# MotorSliderNoPower.net
KiCad netlist of a schematic drawn in EAGLE
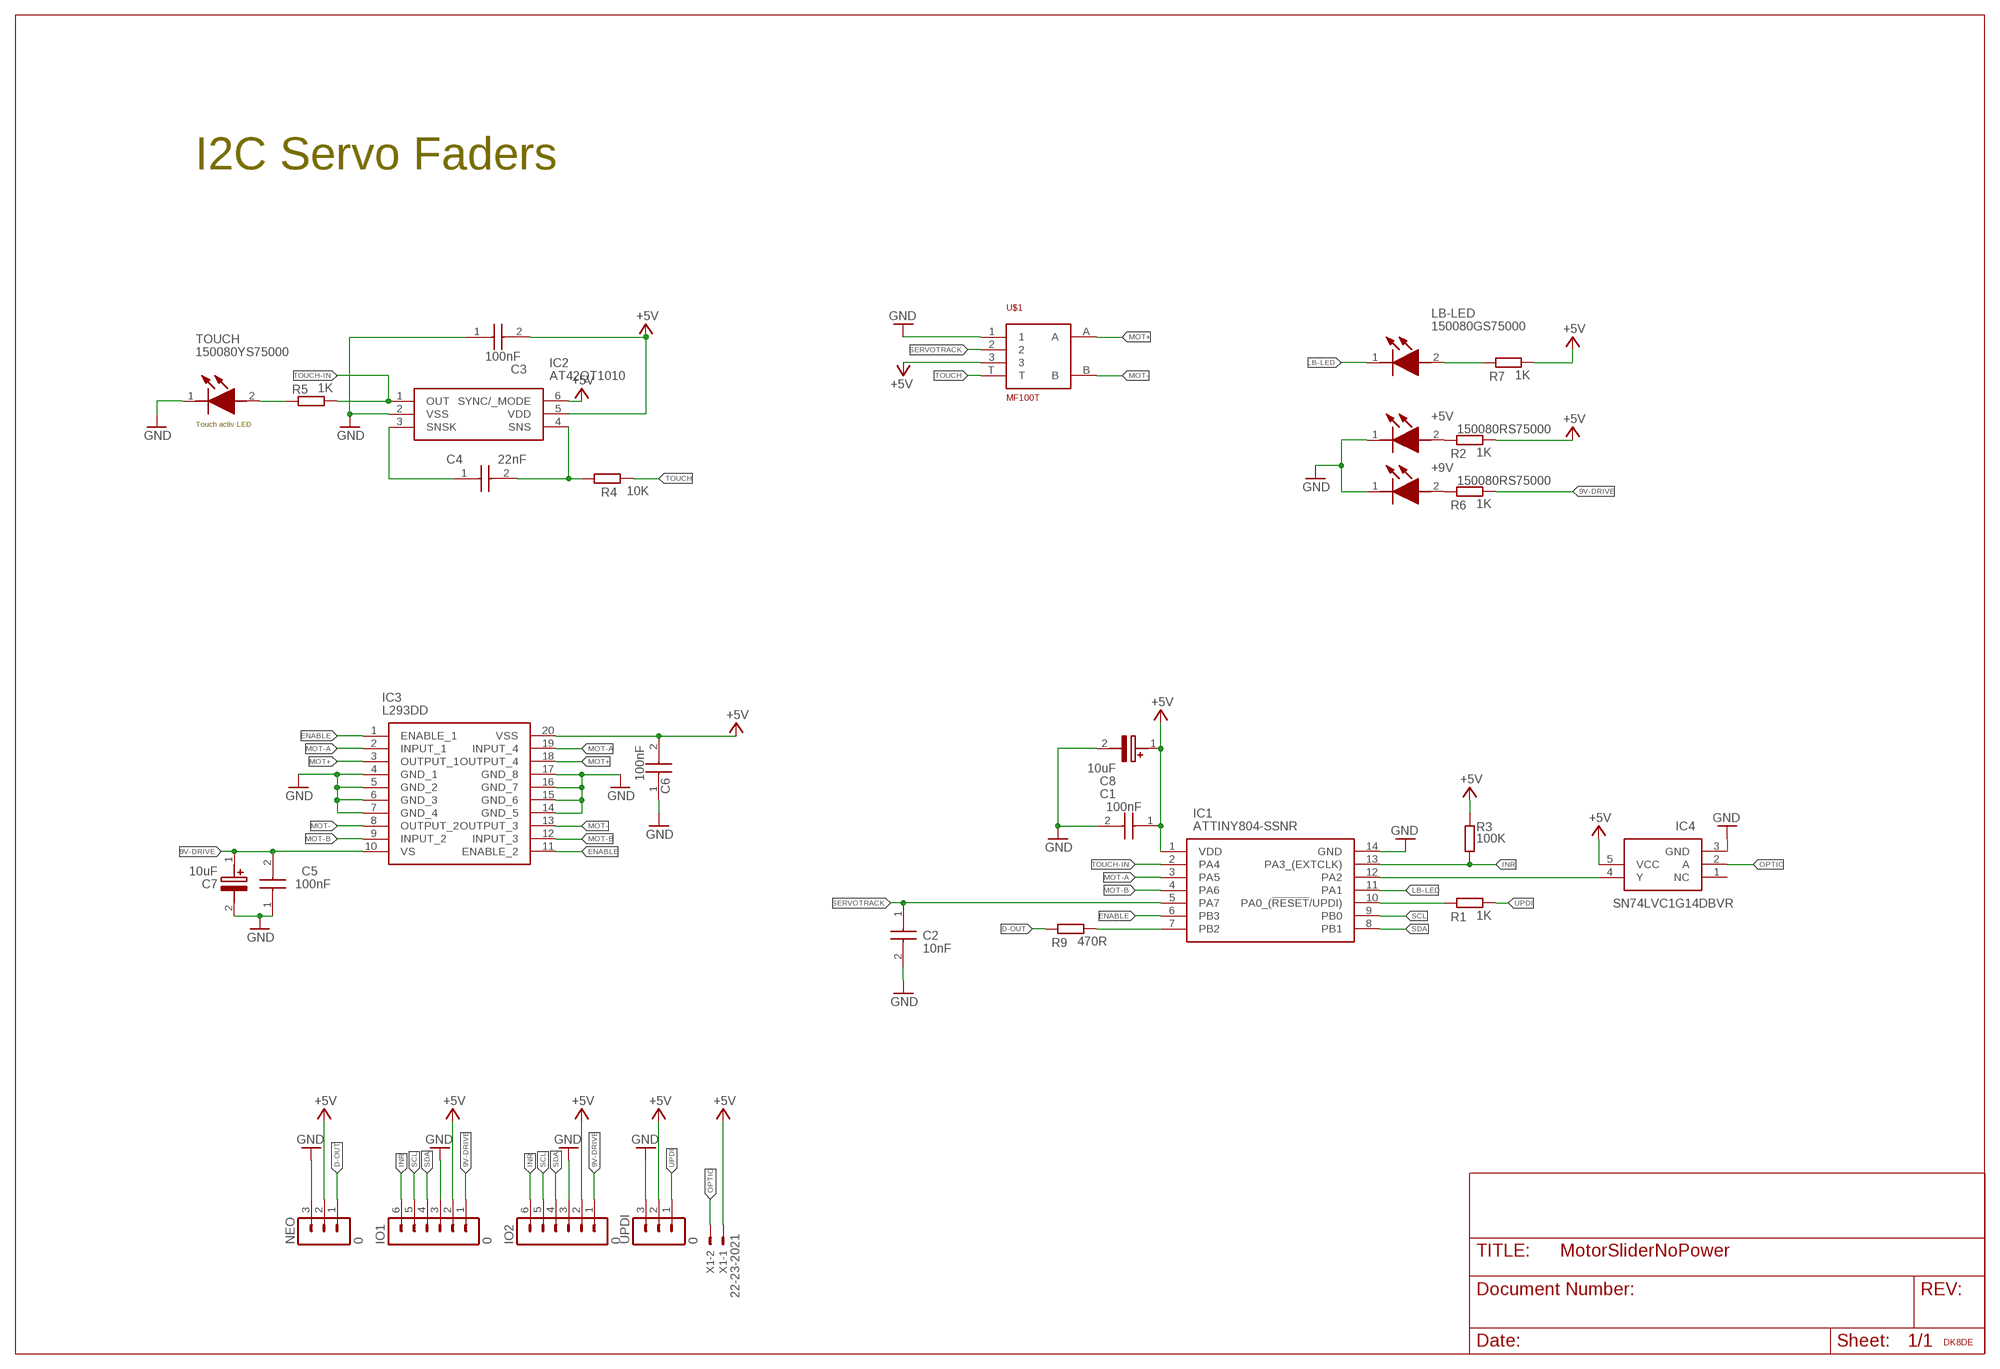
[diagram p0: schematic, sheet 1]

(export (version "E")
  (design (tool "Eeschema 10.0.6"))
  (components
    (comp (ref "+5V")
      (value "150080RS75000")
      (footprint "eagle-import:LEDC2012X80N")
      (fields (field (name "MOUSER_PART_NUMBER") "710-150080RS75000"))
      (libsource (lib "eagle-import") (part "150080RS75000"))
    )
    (comp (ref "+9V")
      (value "150080RS75000")
      (footprint "eagle-import:LEDC2012X80N")
      (fields (field (name "MOUSER_PART_NUMBER") "710-150080RS75000"))
      (libsource (lib "eagle-import") (part "150080RS75000"))
    )
    (comp (ref "C1")
      (value "100nF")
      (footprint "eagle-import:C0805")
      (fields
        (field (name "MANUFACTURER_PART_NUMBER") "C0805C104K1RACTU")
        (field (name "MOUSER_PART_NUMBER") "80-C0805C104K1R")
      )
      (libsource (lib "eagle-import") (part "C0805C104K1RACTU"))
    )
    (comp (ref "C2")
      (value "10nF")
      (footprint "eagle-import:C0805")
      (fields
        (field (name "MANUFACTURER_PART_NUMBER") "C0805Y103K4RACTU")
        (field (name "MOUSER_PART_NUMBER") "80-C0805Y103K4R")
      )
      (libsource (lib "eagle-import") (part "C0805Y103K4RACTU"))
    )
    (comp (ref "C3")
      (value "100nF")
      (footprint "eagle-import:C0805")
      (fields
        (field (name "MANUFACTURER_PART_NUMBER") "C0805C104K1RACTU")
        (field (name "MOUSER_PART_NUMBER") "80-C0805C104K1R")
      )
      (libsource (lib "eagle-import") (part "C0805C104K1RACTU"))
    )
    (comp (ref "C4")
      (value "22nF")
      (footprint "eagle-import:C0805")
      (fields
        (field (name "MANUFACTURER_PART_NUMBER") "C0805C333K4RACTU")
        (field (name "MOUSER_PART_NUMBER") "80-C0805C333K4R")
      )
      (libsource (lib "eagle-import") (part "C0805C333K4RACTU"))
    )
    (comp (ref "C5")
      (value "100nF")
      (footprint "eagle-import:C0805")
      (fields
        (field (name "MANUFACTURER_PART_NUMBER") "C0805C104K1RACTU")
        (field (name "MOUSER_PART_NUMBER") "80-C0805C104K1R")
      )
      (libsource (lib "eagle-import") (part "C0805C104K1RACTU"))
    )
    (comp (ref "C6")
      (value "100nF")
      (footprint "eagle-import:C0805")
      (fields
        (field (name "MANUFACTURER_PART_NUMBER") "C0805C104K1RACTU")
        (field (name "MOUSER_PART_NUMBER") "80-C0805C104K1R")
      )
      (libsource (lib "eagle-import") (part "C0805C104K1RACTU"))
    )
    (comp (ref "C7")
      (value "10uF")
      (footprint "eagle-import:EEE1AA220WR")
      (fields
        (field (name "MANUFACTURER_PART_NUMBER") "EEE-HB1C100R")
        (field (name "MOUSER_PART_NUMBER") "667-EEE-HB1C100R")
      )
      (libsource (lib "eagle-import") (part "EEE-HB1C100R"))
    )
    (comp (ref "C8")
      (value "10uF")
      (footprint "eagle-import:EEE1AA220WR")
      (fields
        (field (name "MANUFACTURER_PART_NUMBER") "EEE-HB1C100R")
        (field (name "MOUSER_PART_NUMBER") "667-EEE-HB1C100R")
      )
      (libsource (lib "eagle-import") (part "EEE-HB1C100R"))
    )
    (comp (ref "IC1")
      (value "ATTINY804-SSNR")
      (footprint "eagle-import:SOIC127P600X175-14N")
      (fields (field (name "MOUSER_PART_NUMBER") "556-ATTINY804-SSNR"))
      (libsource (lib "eagle-import") (part "ATTINY804-SSNR"))
    )
    (comp (ref "IC2")
      (value "AT42QT1010")
      (footprint "eagle-import:SOT95P280X145-6N")
      (fields
        (field (name "MANUFACTURER_PART_NUMBER") "AT42QT1010-TSHR")
        (field (name "MOUSER_PART_NUMBER") "556-AT42QT1010-TSHR")
      )
      (libsource (lib "eagle-import") (part "AT42QT1010-TSHR"))
    )
    (comp (ref "IC3")
      (value "L293DD")
      (footprint "eagle-import:SOIC127P1032X265-20N")
      (fields (field (name "MOUSER_PART_NUMBER") "511-L293DD"))
      (libsource (lib "eagle-import") (part "L293DD"))
    )
    (comp (ref "IC4")
      (value "SN74LVC1G14DBVR")
      (footprint "eagle-import:SOT95P280X145-5N")
      (fields (field (name "MOUSER_PART_NUMBER") "595-SN74LVC1G14DBVR"))
      (libsource (lib "eagle-import") (part "SN74LVC1G14DBVR"))
    )
    (comp (ref "IO1")
      (value "0")
      (footprint "eagle-import:MA06-1")
      (libsource (lib "eagle-import") (part "MA06-1"))
    )
    (comp (ref "IO2")
      (value "0")
      (footprint "eagle-import:MA06-1")
      (libsource (lib "eagle-import") (part "MA06-1"))
    )
    (comp (ref "LB-LED")
      (value "150080GS75000")
      (footprint "eagle-import:LEDM2012X80N")
      (fields (field (name "MOUSER_PART_NUMBER") "710-150080GS75000"))
      (libsource (lib "eagle-import") (part "150080GS75000"))
    )
    (comp (ref "NEO")
      (value "0")
      (footprint "eagle-import:MA03-1")
      (libsource (lib "eagle-import") (part "MA03-1"))
    )
    (comp (ref "R1")
      (value "1K")
      (footprint "eagle-import:R0805")
      (libsource (lib "eagle-import") (part "R-EU_R0805"))
    )
    (comp (ref "R2")
      (value "1K")
      (footprint "eagle-import:R0805")
      (libsource (lib "eagle-import") (part "R-EU_R0805"))
    )
    (comp (ref "R3")
      (value "100K")
      (footprint "eagle-import:R0805")
      (libsource (lib "eagle-import") (part "R-EU_R0805"))
    )
    (comp (ref "R4")
      (value "10K")
      (footprint "eagle-import:R0805")
      (libsource (lib "eagle-import") (part "R-EU_R0805"))
    )
    (comp (ref "R5")
      (value "1K")
      (footprint "eagle-import:R0805")
      (libsource (lib "eagle-import") (part "R-EU_R0805"))
    )
    (comp (ref "R6")
      (value "1K")
      (footprint "eagle-import:R0805")
      (libsource (lib "eagle-import") (part "R-EU_R0805"))
    )
    (comp (ref "R7")
      (value "1K")
      (footprint "eagle-import:R0805")
      (libsource (lib "eagle-import") (part "R-EU_R0805"))
    )
    (comp (ref "R9")
      (value "470R")
      (footprint "eagle-import:R0805")
      (libsource (lib "eagle-import") (part "R-EU_R0805"))
    )
    (comp (ref "TOUCH")
      (value "150080YS75000")
      (footprint "eagle-import:LEDC2012X80N")
      (fields (field (name "MOUSER_PART_NUMBER") "710-150080YS75000"))
      (libsource (lib "eagle-import") (part "150080YS75000"))
    )
    (comp (ref "U$1")
      (value "MF100T")
      (footprint "eagle-import:SM10001NKA0X-HA1")
      (libsource (lib "eagle-import") (part "SM10001NKA0X-HA1"))
    )
    (comp (ref "U$2")
      (value "DK8DESS")
      (footprint "eagle-import:DK8DE_KLEIN")
      (libsource (lib "eagle-import") (part "DK8DESS"))
    )
    (comp (ref "UPDI")
      (value "0")
      (footprint "eagle-import:MA03-1")
      (libsource (lib "eagle-import") (part "MA03-1"))
    )
    (comp (ref "X1")
      (value "22-23-2021")
      (footprint "eagle-import:22-23-2021")
      (fields (field (name "MF") "MOLEX"))
      (libsource (lib "eagle-import") (part "22-23-2021"))
    )
  )
  (nets
    (net (code "1") (name "+5V") (class "Default")
      (node (ref "C1") (pin "1") (pinfunction "1_1") (pintype "bidirectional"))
      (node (ref "C3") (pin "2") (pinfunction "2_2") (pintype "bidirectional"))
      (node (ref "C6") (pin "2") (pinfunction "2_2") (pintype "bidirectional"))
      (node (ref "C8") (pin "1") (pinfunction "+_1") (pintype "bidirectional"))
      (node (ref "IC1") (pin "1") (pinfunction "VDD_1") (pintype "bidirectional"))
      (node (ref "IC2") (pin "5") (pinfunction "VDD_5") (pintype "bidirectional"))
      (node (ref "IC2") (pin "6") (pinfunction "SYNC/_MODE_6") (pintype "bidirectional"))
      (node (ref "IC3") (pin "20") (pinfunction "VSS_20") (pintype "bidirectional"))
      (node (ref "IC4") (pin "5") (pinfunction "VCC_5") (pintype "bidirectional"))
      (node (ref "IO1") (pin "2") (pinfunction "2_2") (pintype "passive"))
      (node (ref "IO2") (pin "2") (pinfunction "2_2") (pintype "passive"))
      (node (ref "NEO") (pin "2") (pinfunction "2_2") (pintype "passive"))
      (node (ref "R2") (pin "2") (pinfunction "2_2") (pintype "passive"))
      (node (ref "R3") (pin "1") (pinfunction "1_1") (pintype "passive"))
      (node (ref "R7") (pin "2") (pinfunction "2_2") (pintype "passive"))
      (node (ref "U$1") (pin "3") (pinfunction "3_3") (pintype "bidirectional"))
      (node (ref "UPDI") (pin "2") (pinfunction "2_2") (pintype "passive"))
      (node (ref "X1") (pin "1") (pinfunction "S_1") (pintype "passive"))
    )
    (net (code "2") (name "9V-DRIVE") (class "Default")
      (node (ref "C5") (pin "2") (pinfunction "2_2") (pintype "bidirectional"))
      (node (ref "C7") (pin "1") (pinfunction "+_1") (pintype "bidirectional"))
      (node (ref "IC3") (pin "10") (pinfunction "VS_10") (pintype "bidirectional"))
      (node (ref "IO1") (pin "1") (pinfunction "1_1") (pintype "passive"))
      (node (ref "IO2") (pin "1") (pinfunction "1_1") (pintype "passive"))
      (node (ref "R6") (pin "2") (pinfunction "2_2") (pintype "passive"))
    )
    (net (code "3") (name "D-OUT") (class "Default")
      (node (ref "NEO") (pin "1") (pinfunction "1_1") (pintype "passive"))
      (node (ref "R9") (pin "1") (pinfunction "1_1") (pintype "passive"))
    )
    (net (code "4") (name "ENABLE") (class "Default")
      (node (ref "IC1") (pin "6") (pinfunction "PB3_6") (pintype "bidirectional"))
      (node (ref "IC3") (pin "1") (pinfunction "ENABLE_1_1") (pintype "bidirectional"))
      (node (ref "IC3") (pin "11") (pinfunction "ENABLE_2_11") (pintype "bidirectional"))
    )
    (net (code "5") (name "GND") (class "Default")
      (node (ref "+5V") (pin "1") (pinfunction "K_1") (pintype "bidirectional"))
      (node (ref "+9V") (pin "1") (pinfunction "K_1") (pintype "bidirectional"))
      (node (ref "C1") (pin "2") (pinfunction "2_2") (pintype "bidirectional"))
      (node (ref "C2") (pin "2") (pinfunction "2_2") (pintype "bidirectional"))
      (node (ref "C3") (pin "1") (pinfunction "1_1") (pintype "bidirectional"))
      (node (ref "C5") (pin "1") (pinfunction "1_1") (pintype "bidirectional"))
      (node (ref "C6") (pin "1") (pinfunction "1_1") (pintype "bidirectional"))
      (node (ref "C7") (pin "2") (pinfunction "-_2") (pintype "bidirectional"))
      (node (ref "C8") (pin "2") (pinfunction "-_2") (pintype "bidirectional"))
      (node (ref "IC1") (pin "14") (pinfunction "GND_14") (pintype "bidirectional"))
      (node (ref "IC2") (pin "2") (pinfunction "VSS_2") (pintype "bidirectional"))
      (node (ref "IC3") (pin "14") (pinfunction "GND_5_14") (pintype "bidirectional"))
      (node (ref "IC3") (pin "15") (pinfunction "GND_6_15") (pintype "bidirectional"))
      (node (ref "IC3") (pin "16") (pinfunction "GND_7_16") (pintype "bidirectional"))
      (node (ref "IC3") (pin "17") (pinfunction "GND_8_17") (pintype "bidirectional"))
      (node (ref "IC3") (pin "4") (pinfunction "GND_1_4") (pintype "bidirectional"))
      (node (ref "IC3") (pin "5") (pinfunction "GND_2_5") (pintype "bidirectional"))
      (node (ref "IC3") (pin "6") (pinfunction "GND_3_6") (pintype "bidirectional"))
      (node (ref "IC3") (pin "7") (pinfunction "GND_4_7") (pintype "bidirectional"))
      (node (ref "IC4") (pin "3") (pinfunction "GND_3") (pintype "bidirectional"))
      (node (ref "IO1") (pin "3") (pinfunction "3_3") (pintype "passive"))
      (node (ref "IO2") (pin "3") (pinfunction "3_3") (pintype "passive"))
      (node (ref "NEO") (pin "3") (pinfunction "3_3") (pintype "passive"))
      (node (ref "TOUCH") (pin "1") (pinfunction "K_1") (pintype "bidirectional"))
      (node (ref "U$1") (pin "1") (pinfunction "1_1") (pintype "bidirectional"))
      (node (ref "UPDI") (pin "3") (pinfunction "3_3") (pintype "passive"))
    )
    (net (code "6") (name "INR") (class "Default")
      (node (ref "IC1") (pin "13") (pinfunction "PA3_(EXTCLK)_13") (pintype "bidirectional"))
      (node (ref "IO1") (pin "6") (pinfunction "6_6") (pintype "passive"))
      (node (ref "IO2") (pin "6") (pinfunction "6_6") (pintype "passive"))
      (node (ref "R3") (pin "2") (pinfunction "2_2") (pintype "passive"))
    )
    (net (code "7") (name "LB-LED") (class "Default")
      (node (ref "IC1") (pin "11") (pinfunction "PA1_11") (pintype "bidirectional"))
      (node (ref "LB-LED") (pin "1") (pinfunction "K_1") (pintype "bidirectional"))
    )
    (net (code "8") (name "MOT+") (class "Default")
      (node (ref "IC3") (pin "18") (pinfunction "OUTPUT_4_18") (pintype "bidirectional"))
      (node (ref "IC3") (pin "3") (pinfunction "OUTPUT_1_3") (pintype "bidirectional"))
      (node (ref "U$1") (pin "A") (pinfunction "A_A") (pintype "bidirectional"))
    )
    (net (code "9") (name "MOT-") (class "Default")
      (node (ref "IC3") (pin "13") (pinfunction "OUTPUT_3_13") (pintype "bidirectional"))
      (node (ref "IC3") (pin "8") (pinfunction "OUTPUT_2_8") (pintype "bidirectional"))
      (node (ref "U$1") (pin "B") (pinfunction "B_B") (pintype "bidirectional"))
    )
    (net (code "10") (name "MOT-A") (class "Default")
      (node (ref "IC1") (pin "3") (pinfunction "PA5_3") (pintype "bidirectional"))
      (node (ref "IC3") (pin "19") (pinfunction "INPUT_4_19") (pintype "bidirectional"))
      (node (ref "IC3") (pin "2") (pinfunction "INPUT_1_2") (pintype "bidirectional"))
    )
    (net (code "11") (name "MOT-B") (class "Default")
      (node (ref "IC1") (pin "4") (pinfunction "PA6_4") (pintype "bidirectional"))
      (node (ref "IC3") (pin "12") (pinfunction "INPUT_3_12") (pintype "bidirectional"))
      (node (ref "IC3") (pin "9") (pinfunction "INPUT_2_9") (pintype "bidirectional"))
    )
    (net (code "12") (name "Net-(+5V-A)") (class "Default")
      (node (ref "+5V") (pin "2") (pinfunction "A_2") (pintype "bidirectional"))
      (node (ref "R2") (pin "1") (pinfunction "1_1") (pintype "passive"))
    )
    (net (code "13") (name "Net-(+9V-A)") (class "Default")
      (node (ref "+9V") (pin "2") (pinfunction "A_2") (pintype "bidirectional"))
      (node (ref "R6") (pin "1") (pinfunction "1_1") (pintype "passive"))
    )
    (net (code "14") (name "Net-(IC1-PA0_(~{RESET}{slash}UPDI))") (class "Default")
      (node (ref "IC1") (pin "10") (pinfunction "PA0_(~{RESET}/UPDI)_10") (pintype "bidirectional"))
      (node (ref "R1") (pin "1") (pinfunction "1_1") (pintype "passive"))
    )
    (net (code "15") (name "Net-(IC1-PA2)") (class "Default")
      (node (ref "IC1") (pin "12") (pinfunction "PA2_12") (pintype "bidirectional"))
      (node (ref "IC4") (pin "4") (pinfunction "Y_4") (pintype "bidirectional"))
    )
    (net (code "16") (name "Net-(IC1-PB2)") (class "Default")
      (node (ref "IC1") (pin "7") (pinfunction "PB2_7") (pintype "bidirectional"))
      (node (ref "R9") (pin "2") (pinfunction "2_2") (pintype "passive"))
    )
    (net (code "17") (name "Net-(IC2-SNS)") (class "Default")
      (node (ref "C4") (pin "2") (pinfunction "2_2") (pintype "bidirectional"))
      (node (ref "IC2") (pin "4") (pinfunction "SNS_4") (pintype "bidirectional"))
      (node (ref "R4") (pin "1") (pinfunction "1_1") (pintype "passive"))
    )
    (net (code "18") (name "Net-(IC2-SNSK)") (class "Default")
      (node (ref "C4") (pin "1") (pinfunction "1_1") (pintype "bidirectional"))
      (node (ref "IC2") (pin "3") (pinfunction "SNSK_3") (pintype "bidirectional"))
    )
    (net (code "19") (name "Net-(LB-LED-A)") (class "Default")
      (node (ref "LB-LED") (pin "2") (pinfunction "A_2") (pintype "bidirectional"))
      (node (ref "R7") (pin "1") (pinfunction "1_1") (pintype "passive"))
    )
    (net (code "20") (name "Net-(TOUCH-A)") (class "Default")
      (node (ref "R5") (pin "1") (pinfunction "1_1") (pintype "passive"))
      (node (ref "TOUCH") (pin "2") (pinfunction "A_2") (pintype "bidirectional"))
    )
    (net (code "21") (name "OPTIO") (class "Default")
      (node (ref "IC4") (pin "2") (pinfunction "A_2") (pintype "bidirectional"))
      (node (ref "X1") (pin "2") (pinfunction "S_2") (pintype "passive"))
    )
    (net (code "22") (name "SCL") (class "Default")
      (node (ref "IC1") (pin "9") (pinfunction "PB0_9") (pintype "bidirectional"))
      (node (ref "IO1") (pin "5") (pinfunction "5_5") (pintype "passive"))
      (node (ref "IO2") (pin "5") (pinfunction "5_5") (pintype "passive"))
    )
    (net (code "23") (name "SDA") (class "Default")
      (node (ref "IC1") (pin "8") (pinfunction "PB1_8") (pintype "bidirectional"))
      (node (ref "IO1") (pin "4") (pinfunction "4_4") (pintype "passive"))
      (node (ref "IO2") (pin "4") (pinfunction "4_4") (pintype "passive"))
    )
    (net (code "24") (name "SERVOTRACK") (class "Default")
      (node (ref "C2") (pin "1") (pinfunction "1_1") (pintype "bidirectional"))
      (node (ref "IC1") (pin "5") (pinfunction "PA7_5") (pintype "bidirectional"))
      (node (ref "U$1") (pin "2") (pinfunction "2_2") (pintype "bidirectional"))
    )
    (net (code "25") (name "TOUCH") (class "Default")
      (node (ref "R4") (pin "2") (pinfunction "2_2") (pintype "passive"))
      (node (ref "U$1") (pin "T") (pinfunction "T_T") (pintype "bidirectional"))
    )
    (net (code "26") (name "TOUCH-IN") (class "Default")
      (node (ref "IC1") (pin "2") (pinfunction "PA4_2") (pintype "bidirectional"))
      (node (ref "IC2") (pin "1") (pinfunction "OUT_1") (pintype "bidirectional"))
      (node (ref "R5") (pin "2") (pinfunction "2_2") (pintype "passive"))
    )
    (net (code "27") (name "UPDI") (class "Default")
      (node (ref "R1") (pin "2") (pinfunction "2_2") (pintype "passive"))
      (node (ref "UPDI") (pin "1") (pinfunction "1_1") (pintype "passive"))
    )
    (net (code "28") (name "unconnected-(IC4-NC-Pad1)") (class "Default")
      (node (ref "IC4") (pin "1") (pinfunction "NC_1") (pintype "no_connect"))
    )
  )
)
